# pcb-bldc-servo-2.net
KiCad netlist of a schematic drawn in EAGLE
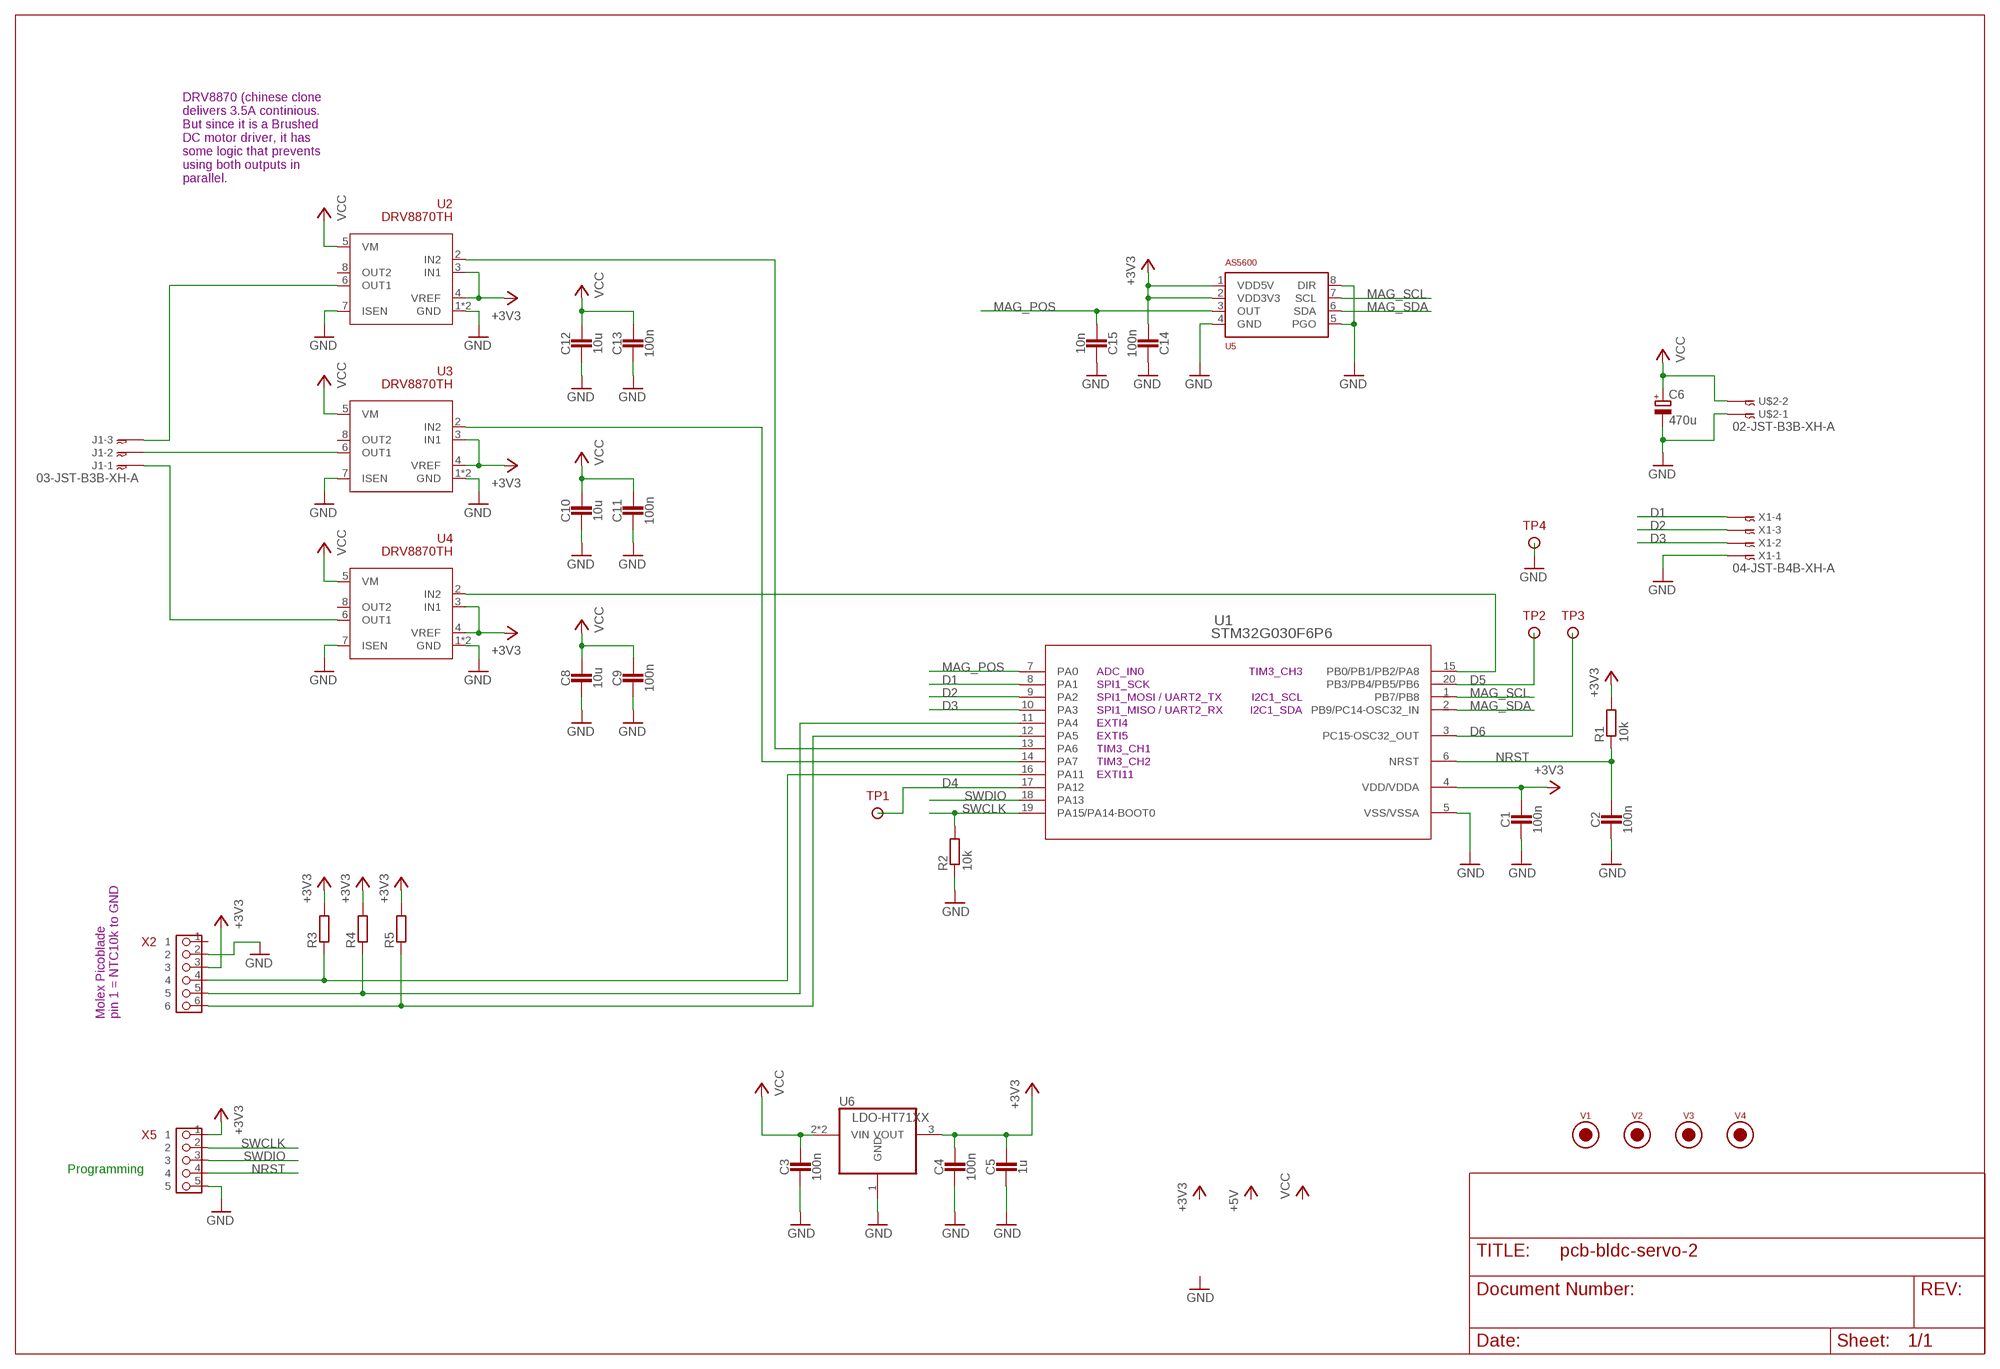
[diagram p0: schematic, sheet 1]

(export (version "E")
  (design (tool "Eeschema 10.0.6"))
  (components
    (comp (ref "C1")
      (value "100n")
      (footprint "eagle-import:0603_CAP")
      (libsource (lib "eagle-import") (part "CAPACITOR0603_CAP"))
    )
    (comp (ref "C2")
      (value "100n")
      (footprint "eagle-import:0603_CAP")
      (libsource (lib "eagle-import") (part "CAPACITOR0603_CAP"))
    )
    (comp (ref "C3")
      (value "100n")
      (footprint "eagle-import:0603_CAP")
      (libsource (lib "eagle-import") (part "CAPACITOR0603_CAP"))
    )
    (comp (ref "C4")
      (value "100n")
      (footprint "eagle-import:0603_CAP")
      (libsource (lib "eagle-import") (part "CAPACITOR0603_CAP"))
    )
    (comp (ref "C5")
      (value "1u")
      (footprint "eagle-import:0603_CAP")
      (libsource (lib "eagle-import") (part "CAPACITOR0603_CAP"))
    )
    (comp (ref "C6")
      (value "470u")
      (footprint "eagle-import:153CLV-1010")
      (libsource (lib "eagle-import") (part "CPOL-EU153CLV-1010"))
    )
    (comp (ref "C8")
      (value "10u")
      (footprint "eagle-import:1206_CAP")
      (libsource (lib "eagle-import") (part "CAPACITOR1206_CAP"))
    )
    (comp (ref "C9")
      (value "100n")
      (footprint "eagle-import:0603_CAP")
      (libsource (lib "eagle-import") (part "CAPACITOR0603_CAP"))
    )
    (comp (ref "C10")
      (value "10u")
      (footprint "eagle-import:1206_CAP")
      (libsource (lib "eagle-import") (part "CAPACITOR1206_CAP"))
    )
    (comp (ref "C11")
      (value "100n")
      (footprint "eagle-import:0603_CAP")
      (libsource (lib "eagle-import") (part "CAPACITOR0603_CAP"))
    )
    (comp (ref "C12")
      (value "10u")
      (footprint "eagle-import:1206_CAP")
      (libsource (lib "eagle-import") (part "CAPACITOR1206_CAP"))
    )
    (comp (ref "C13")
      (value "100n")
      (footprint "eagle-import:0603_CAP")
      (libsource (lib "eagle-import") (part "CAPACITOR0603_CAP"))
    )
    (comp (ref "C14")
      (value "100n")
      (footprint "eagle-import:0603_CAP")
      (libsource (lib "eagle-import") (part "CAPACITOR0603_CAP"))
    )
    (comp (ref "C15")
      (value "10n")
      (footprint "eagle-import:0603_CAP")
      (libsource (lib "eagle-import") (part "CAPACITOR0603_CAP"))
    )
    (comp (ref "J1")
      (value "03-JST-B3B-XH-A")
      (footprint "eagle-import:B3B-XH")
      (libsource (lib "eagle-import") (part "03-JST-B3B-XH-A"))
    )
    (comp (ref "R1")
      (value "10k")
      (footprint "eagle-import:0603-RES")
      (libsource (lib "eagle-import") (part "RESISTOR0603_RES"))
    )
    (comp (ref "R2")
      (value "10k")
      (footprint "eagle-import:0603-RES")
      (libsource (lib "eagle-import") (part "RESISTOR0603_RES"))
    )
    (comp (ref "R3")
      (value "RESISTOR0603_RES")
      (footprint "eagle-import:0603-RES")
      (libsource (lib "eagle-import") (part "RESISTOR0603_RES"))
    )
    (comp (ref "R4")
      (value "RESISTOR0603_RES")
      (footprint "eagle-import:0603-RES")
      (libsource (lib "eagle-import") (part "RESISTOR0603_RES"))
    )
    (comp (ref "R5")
      (value "RESISTOR0603_RES")
      (footprint "eagle-import:0603-RES")
      (libsource (lib "eagle-import") (part "RESISTOR0603_RES"))
    )
    (comp (ref "TP1")
      (value "TESTPIN1MM")
      (footprint "eagle-import:PIN-SMD-1X1-TEST_1M0")
      (libsource (lib "eagle-import") (part "TESTPIN1MM"))
    )
    (comp (ref "TP2")
      (value "TESTPIN1MM")
      (footprint "eagle-import:PIN-SMD-1X1-TEST_1M0")
      (libsource (lib "eagle-import") (part "TESTPIN1MM"))
    )
    (comp (ref "TP3")
      (value "TESTPIN1MM")
      (footprint "eagle-import:PIN-SMD-1X1-TEST_1M0")
      (libsource (lib "eagle-import") (part "TESTPIN1MM"))
    )
    (comp (ref "TP4")
      (value "TESTPIN1MM")
      (footprint "eagle-import:PIN-SMD-1X1-TEST_1M0")
      (libsource (lib "eagle-import") (part "TESTPIN1MM"))
    )
    (comp (ref "U$2")
      (value "02-JST-B3B-XH-A")
      (footprint "eagle-import:B2B-XH")
      (libsource (lib "eagle-import") (part "02-JST-B3B-XH-A"))
    )
    (comp (ref "U1")
      (value "STM32G030F6P6")
      (footprint "eagle-import:TSSOP20")
      (fields (field (name "COPYRIGHT") "Copyright (C) 2024 Ultra Librarian. All rights reserved."))
      (libsource (lib "eagle-import") (part "STM32G030F6P6"))
    )
    (comp (ref "U2")
      (value "DRV8870TH")
      (footprint "eagle-import:SOIC-8-THERM")
      (libsource (lib "eagle-import") (part "DRV8870TH"))
    )
    (comp (ref "U3")
      (value "DRV8870TH")
      (footprint "eagle-import:SOIC-8-THERM")
      (libsource (lib "eagle-import") (part "DRV8870TH"))
    )
    (comp (ref "U4")
      (value "DRV8870TH")
      (footprint "eagle-import:SOIC-8-THERM")
      (libsource (lib "eagle-import") (part "DRV8870TH"))
    )
    (comp (ref "U5")
      (value "AS5600")
      (footprint "eagle-import:SOIC-8")
      (libsource (lib "eagle-import") (part "AS5600"))
    )
    (comp (ref "U6")
      (value "LDO-HT71XX")
      (footprint "eagle-import:SOT-89")
      (libsource (lib "eagle-import") (part "LDO-HT71XX"))
    )
    (comp (ref "V1")
      (value "FIDUCIAL2MM")
      (footprint "eagle-import:FIDUCIAL_2MM")
      (libsource (lib "eagle-import") (part "FIDUCIAL2MM"))
    )
    (comp (ref "V2")
      (value "FIDUCIAL2MM")
      (footprint "eagle-import:FIDUCIAL_2MM")
      (libsource (lib "eagle-import") (part "FIDUCIAL2MM"))
    )
    (comp (ref "V3")
      (value "FIDUCIAL2MM")
      (footprint "eagle-import:FIDUCIAL_2MM")
      (libsource (lib "eagle-import") (part "FIDUCIAL2MM"))
    )
    (comp (ref "V4")
      (value "FIDUCIAL2MM")
      (footprint "eagle-import:FIDUCIAL_2MM")
      (libsource (lib "eagle-import") (part "FIDUCIAL2MM"))
    )
    (comp (ref "X1")
      (value "04-JST-B4B-XH-A")
      (footprint "eagle-import:B4B-XH")
      (libsource (lib "eagle-import") (part "04-JST-B4B-XH-A"))
    )
    (comp (ref "X2")
      (value "PIN_6X1")
      (footprint "eagle-import:PIN_6X1_MOLEX_PICOBLADE")
      (libsource (lib "eagle-import") (part "PIN_6X1"))
    )
    (comp (ref "X5")
      (value "PIN_5X1HD")
      (footprint "eagle-import:PIN_5X1_HD")
      (libsource (lib "eagle-import") (part "PIN_5X1HD"))
    )
  )
  (nets
    (net (code "1") (name "+3V3") (class "Default")
      (node (ref "C1") (pin "1") (pinfunction "1_1") (pintype "bidirectional"))
      (node (ref "C14") (pin "1") (pinfunction "1_1") (pintype "bidirectional"))
      (node (ref "C4") (pin "1") (pinfunction "1_1") (pintype "bidirectional"))
      (node (ref "C5") (pin "1") (pinfunction "1_1") (pintype "bidirectional"))
      (node (ref "R1") (pin "2") (pinfunction "2_2") (pintype "passive"))
      (node (ref "R3") (pin "2") (pinfunction "2_2") (pintype "passive"))
      (node (ref "R4") (pin "2") (pinfunction "2_2") (pintype "passive"))
      (node (ref "R5") (pin "2") (pinfunction "2_2") (pintype "passive"))
      (node (ref "U1") (pin "4") (pinfunction "VDD/VDDA_4") (pintype "power_in"))
      (node (ref "U2") (pin "3") (pinfunction "IN1_3") (pintype "bidirectional"))
      (node (ref "U2") (pin "4") (pinfunction "VREF_4") (pintype "bidirectional"))
      (node (ref "U3") (pin "3") (pinfunction "IN1_3") (pintype "bidirectional"))
      (node (ref "U3") (pin "4") (pinfunction "VREF_4") (pintype "bidirectional"))
      (node (ref "U4") (pin "3") (pinfunction "IN1_3") (pintype "bidirectional"))
      (node (ref "U4") (pin "4") (pinfunction "VREF_4") (pintype "bidirectional"))
      (node (ref "U5") (pin "1") (pinfunction "VDD5V_1") (pintype "bidirectional"))
      (node (ref "U5") (pin "2") (pinfunction "VDD3V3_2") (pintype "bidirectional"))
      (node (ref "U6") (pin "3") (pinfunction "VOUT_3") (pintype "output"))
      (node (ref "X2") (pin "3") (pinfunction "3_3") (pintype "bidirectional"))
      (node (ref "X5") (pin "1") (pinfunction "1_1") (pintype "bidirectional"))
    )
    (net (code "3") (name "/D1") (class "Default")
      (node (ref "U1") (pin "8") (pinfunction "PA1_8") (pintype "bidirectional"))
      (node (ref "X1") (pin "P$4") (pinfunction "1_P$4") (pintype "passive"))
    )
    (net (code "4") (name "/D2") (class "Default")
      (node (ref "U1") (pin "9") (pinfunction "PA2_9") (pintype "bidirectional"))
      (node (ref "X1") (pin "P$3") (pinfunction "1_P$3") (pintype "passive"))
    )
    (net (code "5") (name "/D3") (class "Default")
      (node (ref "U1") (pin "10") (pinfunction "PA3_10") (pintype "bidirectional"))
      (node (ref "X1") (pin "P$2") (pinfunction "1_P$2") (pintype "passive"))
    )
    (net (code "6") (name "/D4") (class "Default")
      (node (ref "TP1") (pin "1") (pinfunction "1_1") (pintype "bidirectional"))
      (node (ref "U1") (pin "17") (pinfunction "PA12_17") (pintype "bidirectional"))
    )
    (net (code "7") (name "/D5") (class "Default")
      (node (ref "TP2") (pin "1") (pinfunction "1_1") (pintype "bidirectional"))
      (node (ref "U1") (pin "20") (pinfunction "PB3/PB4/PB5/PB6_20") (pintype "bidirectional"))
    )
    (net (code "8") (name "/D6") (class "Default")
      (node (ref "TP3") (pin "1") (pinfunction "1_1") (pintype "bidirectional"))
      (node (ref "U1") (pin "3") (pinfunction "PC15-OSC32_OUT_3") (pintype "bidirectional"))
    )
    (net (code "9") (name "/MAG_POS") (class "Default")
      (node (ref "C15") (pin "1") (pinfunction "1_1") (pintype "bidirectional"))
      (node (ref "U1") (pin "7") (pinfunction "PA0_7") (pintype "bidirectional"))
      (node (ref "U5") (pin "3") (pinfunction "OUT_3") (pintype "bidirectional"))
    )
    (net (code "10") (name "/MAG_SCL") (class "Default")
      (node (ref "U1") (pin "1") (pinfunction "PB7/PB8_1") (pintype "bidirectional"))
      (node (ref "U5") (pin "7") (pinfunction "SCL_7") (pintype "bidirectional"))
    )
    (net (code "11") (name "/MAG_SDA") (class "Default")
      (node (ref "U1") (pin "2") (pinfunction "PB9/PC14-OSC32_IN_2") (pintype "bidirectional"))
      (node (ref "U5") (pin "6") (pinfunction "SDA_6") (pintype "bidirectional"))
    )
    (net (code "12") (name "/NRST") (class "Default")
      (node (ref "C2") (pin "1") (pinfunction "1_1") (pintype "bidirectional"))
      (node (ref "R1") (pin "1") (pinfunction "1_1") (pintype "passive"))
      (node (ref "U1") (pin "6") (pinfunction "NRST_6") (pintype "bidirectional"))
      (node (ref "X5") (pin "4") (pinfunction "4_4") (pintype "bidirectional"))
    )
    (net (code "13") (name "/SWCLK") (class "Default")
      (node (ref "R2") (pin "2") (pinfunction "2_2") (pintype "passive"))
      (node (ref "U1") (pin "19") (pinfunction "PA15/PA14-BOOT0_19") (pintype "bidirectional"))
      (node (ref "X5") (pin "2") (pinfunction "2_2") (pintype "bidirectional"))
    )
    (net (code "14") (name "/SWDIO") (class "Default")
      (node (ref "U1") (pin "18") (pinfunction "PA13_18") (pintype "bidirectional"))
      (node (ref "X5") (pin "3") (pinfunction "3_3") (pintype "bidirectional"))
    )
    (net (code "15") (name "GND") (class "Default")
      (node (ref "C1") (pin "2") (pinfunction "2_2") (pintype "bidirectional"))
      (node (ref "C10") (pin "2") (pinfunction "2_2") (pintype "bidirectional"))
      (node (ref "C11") (pin "2") (pinfunction "2_2") (pintype "bidirectional"))
      (node (ref "C12") (pin "2") (pinfunction "2_2") (pintype "bidirectional"))
      (node (ref "C13") (pin "2") (pinfunction "2_2") (pintype "bidirectional"))
      (node (ref "C14") (pin "2") (pinfunction "2_2") (pintype "bidirectional"))
      (node (ref "C15") (pin "2") (pinfunction "2_2") (pintype "bidirectional"))
      (node (ref "C2") (pin "2") (pinfunction "2_2") (pintype "bidirectional"))
      (node (ref "C3") (pin "2") (pinfunction "2_2") (pintype "bidirectional"))
      (node (ref "C4") (pin "2") (pinfunction "2_2") (pintype "bidirectional"))
      (node (ref "C5") (pin "2") (pinfunction "2_2") (pintype "bidirectional"))
      (node (ref "C6") (pin "-") (pinfunction "-_-") (pintype "passive"))
      (node (ref "C8") (pin "2") (pinfunction "2_2") (pintype "bidirectional"))
      (node (ref "C9") (pin "2") (pinfunction "2_2") (pintype "bidirectional"))
      (node (ref "R2") (pin "1") (pinfunction "1_1") (pintype "passive"))
      (node (ref "TP4") (pin "1") (pinfunction "1_1") (pintype "bidirectional"))
      (node (ref "U$2") (pin "P$1") (pinfunction "1_P$1") (pintype "passive"))
      (node (ref "U1") (pin "5") (pinfunction "VSS/VSSA_5") (pintype "power_in"))
      (node (ref "U2") (pin "1") (pinfunction "GND_1") (pintype "bidirectional"))
      (node (ref "U2") (pin "7") (pinfunction "ISEN_7") (pintype "bidirectional"))
      (node (ref "U2") (pin "9") (pinfunction "GND_9") (pintype "bidirectional"))
      (node (ref "U3") (pin "1") (pinfunction "GND_1") (pintype "bidirectional"))
      (node (ref "U3") (pin "7") (pinfunction "ISEN_7") (pintype "bidirectional"))
      (node (ref "U3") (pin "9") (pinfunction "GND_9") (pintype "bidirectional"))
      (node (ref "U4") (pin "1") (pinfunction "GND_1") (pintype "bidirectional"))
      (node (ref "U4") (pin "7") (pinfunction "ISEN_7") (pintype "bidirectional"))
      (node (ref "U4") (pin "9") (pinfunction "GND_9") (pintype "bidirectional"))
      (node (ref "U5") (pin "4") (pinfunction "GND_4") (pintype "bidirectional"))
      (node (ref "U5") (pin "5") (pinfunction "PGO_5") (pintype "bidirectional"))
      (node (ref "U5") (pin "8") (pinfunction "DIR_8") (pintype "bidirectional"))
      (node (ref "U6") (pin "1") (pinfunction "GND_1") (pintype "power_in"))
      (node (ref "X1") (pin "P$1") (pinfunction "1_P$1") (pintype "passive"))
      (node (ref "X2") (pin "2") (pinfunction "2_2") (pintype "bidirectional"))
      (node (ref "X5") (pin "5") (pinfunction "5_5") (pintype "bidirectional"))
    )
    (net (code "16") (name "Net-(J1A-1)") (class "Default")
      (node (ref "J1") (pin "P$1") (pinfunction "1_P$1") (pintype "passive"))
      (node (ref "U4") (pin "6") (pinfunction "OUT1_6") (pintype "bidirectional"))
    )
    (net (code "17") (name "Net-(J1B-1)") (class "Default")
      (node (ref "J1") (pin "P$2") (pinfunction "1_P$2") (pintype "passive"))
      (node (ref "U3") (pin "6") (pinfunction "OUT1_6") (pintype "bidirectional"))
    )
    (net (code "18") (name "Net-(J1C-1)") (class "Default")
      (node (ref "J1") (pin "P$3") (pinfunction "1_P$3") (pintype "passive"))
      (node (ref "U2") (pin "6") (pinfunction "OUT1_6") (pintype "bidirectional"))
    )
    (net (code "19") (name "Net-(U1-PA4)") (class "Default")
      (node (ref "R4") (pin "1") (pinfunction "1_1") (pintype "passive"))
      (node (ref "U1") (pin "11") (pinfunction "PA4_11") (pintype "bidirectional"))
      (node (ref "X2") (pin "5") (pinfunction "5_5") (pintype "bidirectional"))
    )
    (net (code "20") (name "Net-(U1-PA5)") (class "Default")
      (node (ref "R5") (pin "1") (pinfunction "1_1") (pintype "passive"))
      (node (ref "U1") (pin "12") (pinfunction "PA5_12") (pintype "bidirectional"))
      (node (ref "X2") (pin "6") (pinfunction "6_6") (pintype "bidirectional"))
    )
    (net (code "21") (name "Net-(U1-PA6)") (class "Default")
      (node (ref "U1") (pin "13") (pinfunction "PA6_13") (pintype "bidirectional"))
      (node (ref "U2") (pin "2") (pinfunction "IN2_2") (pintype "bidirectional"))
    )
    (net (code "22") (name "Net-(U1-PA7)") (class "Default")
      (node (ref "U1") (pin "14") (pinfunction "PA7_14") (pintype "bidirectional"))
      (node (ref "U3") (pin "2") (pinfunction "IN2_2") (pintype "bidirectional"))
    )
    (net (code "23") (name "Net-(U1-PA11)") (class "Default")
      (node (ref "R3") (pin "1") (pinfunction "1_1") (pintype "passive"))
      (node (ref "U1") (pin "16") (pinfunction "PA11_16") (pintype "bidirectional"))
      (node (ref "X2") (pin "4") (pinfunction "4_4") (pintype "bidirectional"))
    )
    (net (code "24") (name "Net-(U1-PB0{slash}PB1{slash}PB2{slash}PA8)") (class "Default")
      (node (ref "U1") (pin "15") (pinfunction "PB0/PB1/PB2/PA8_15") (pintype "bidirectional"))
      (node (ref "U4") (pin "2") (pinfunction "IN2_2") (pintype "bidirectional"))
    )
    (net (code "25") (name "VCC") (class "Default")
      (node (ref "C10") (pin "1") (pinfunction "1_1") (pintype "bidirectional"))
      (node (ref "C11") (pin "1") (pinfunction "1_1") (pintype "bidirectional"))
      (node (ref "C12") (pin "1") (pinfunction "1_1") (pintype "bidirectional"))
      (node (ref "C13") (pin "1") (pinfunction "1_1") (pintype "bidirectional"))
      (node (ref "C3") (pin "1") (pinfunction "1_1") (pintype "bidirectional"))
      (node (ref "C6") (pin "+") (pinfunction "+_+") (pintype "passive"))
      (node (ref "C8") (pin "1") (pinfunction "1_1") (pintype "bidirectional"))
      (node (ref "C9") (pin "1") (pinfunction "1_1") (pintype "bidirectional"))
      (node (ref "U$2") (pin "P$2") (pinfunction "1_P$2") (pintype "passive"))
      (node (ref "U2") (pin "5") (pinfunction "VM_5") (pintype "bidirectional"))
      (node (ref "U3") (pin "5") (pinfunction "VM_5") (pintype "bidirectional"))
      (node (ref "U4") (pin "5") (pinfunction "VM_5") (pintype "bidirectional"))
      (node (ref "U6") (pin "2") (pinfunction "VIN_2") (pintype "input"))
      (node (ref "U6") (pin "2@1") (pinfunction "VIN_2@1") (pintype "input"))
    )
    (net (code "26") (name "unconnected-(U2-OUT2-Pad8)") (class "Default")
      (node (ref "U2") (pin "8") (pinfunction "OUT2_8") (pintype "bidirectional"))
    )
    (net (code "27") (name "unconnected-(U3-OUT2-Pad8)") (class "Default")
      (node (ref "U3") (pin "8") (pinfunction "OUT2_8") (pintype "bidirectional"))
    )
    (net (code "28") (name "unconnected-(U4-OUT2-Pad8)") (class "Default")
      (node (ref "U4") (pin "8") (pinfunction "OUT2_8") (pintype "bidirectional"))
    )
    (net (code "29") (name "unconnected-(X2-Pad1)") (class "Default")
      (node (ref "X2") (pin "1") (pinfunction "1_1") (pintype "bidirectional"))
    )
  )
)
